# Controller.net
KiCad netlist of a schematic drawn in Altium Designer
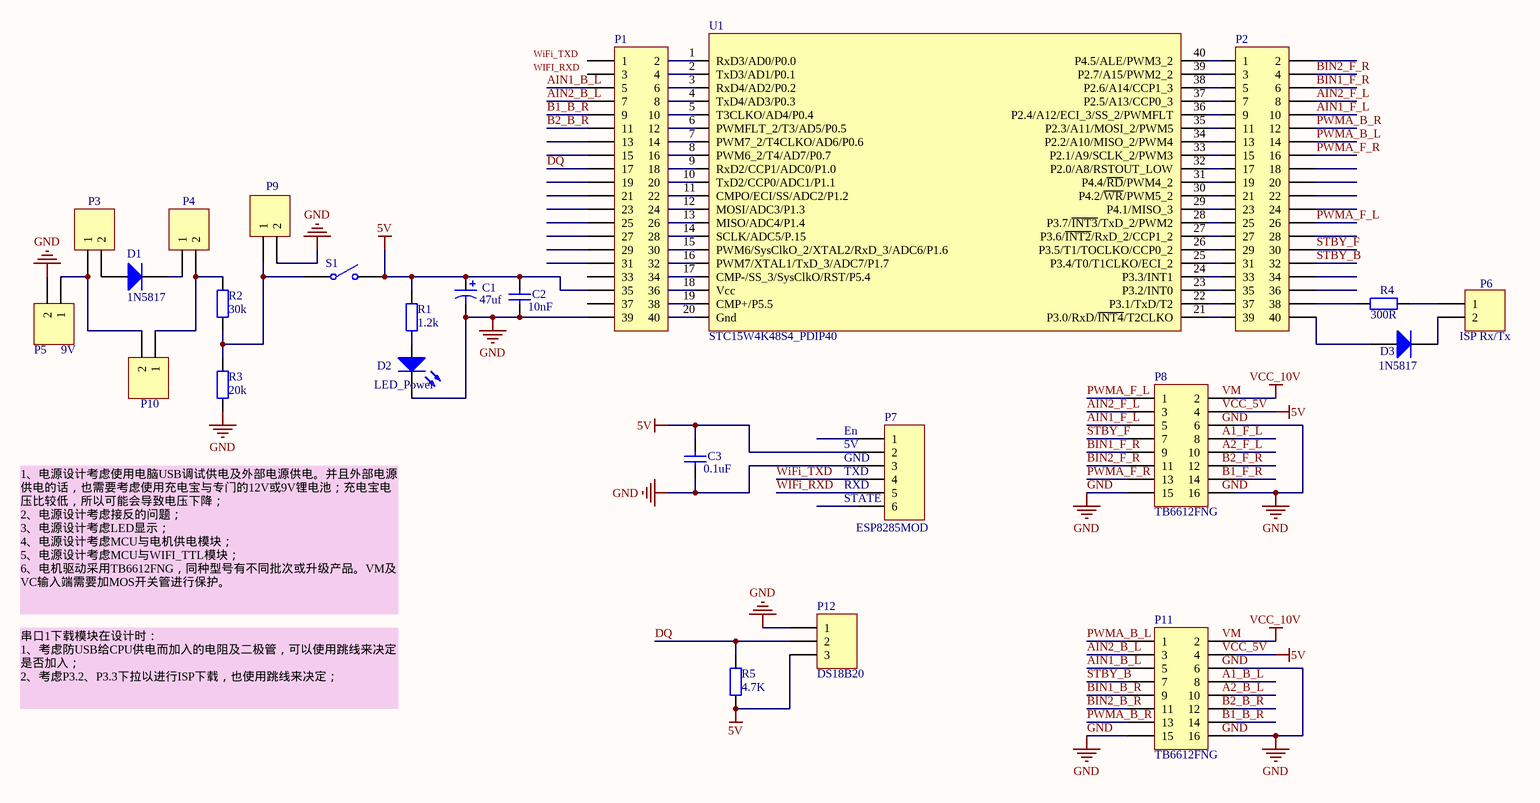
[diagram p0: Controller.SchDoc]

(export (version "E")
  (design (tool "Eeschema 10.0.6"))
  (components
    (comp (ref "C1")
      (value "47uf")
      (footprint "RB7.6-15")
      (description "Polarized Capacitor (Radial)")
      (fields (field (name "Comment") "Cap Pol1") (field (name "PUBLISHER") "Altium Limited"))
      (libsource (lib "Miscellaneous Devices") (part "Cap Pol1"))
    )
    (comp (ref "C2")
      (value "10nF")
      (footprint "RAD-0.3")
      (description "Capacitor")
      (fields (field (name "Comment") "Cap") (field (name "PUBLISHER") "Altium Limited"))
      (libsource (lib "Miscellaneous Devices") (part "Cap"))
    )
    (comp (ref "C3")
      (value "0.1uF")
      (footprint "RAD-0.3")
      (description "Capacitor")
      (fields (field (name "Comment") "Cap") (field (name "PUBLISHER") "Altium Limited"))
      (libsource (lib "Miscellaneous Devices") (part "Cap"))
    )
    (comp (ref "D1")
      (value "1N5817")
      (footprint "DO-35")
      (description "High Conductance Fast Diode")
      (fields (field (name "PUBLISHER") "Altium Limited"))
      (libsource (lib "Miscellaneous Devices") (part "Diode 1N914"))
    )
    (comp (ref "D2")
      (value "LED_Power")
      (footprint "LED-0")
      (description "Typical INFRARED GaAs LED")
      (fields (field (name "PUBLISHER") "Altium Limited"))
      (libsource (lib "Miscellaneous Devices") (part "LED0"))
    )
    (comp (ref "D3")
      (value "1N5817")
      (footprint "DO-35")
      (description "High Conductance Fast Diode")
      (fields (field (name "PUBLISHER") "Altium Limited"))
      (libsource (lib "Miscellaneous Devices") (part "Diode 1N914"))
    )
    (comp (ref "P1")
      (value "Header 20X2")
      (footprint "HDR2X20")
      (description "Header, 20-Pin, Dual row")
      (fields (field (name "PUBLISHER") "Altium Limited"))
      (libsource (lib "Miscellaneous Connectors") (part "Header 20X2"))
    )
    (comp (ref "P2")
      (value "Header 20X2")
      (footprint "HDR2X20")
      (description "Header, 20-Pin, Dual row")
      (fields (field (name "PUBLISHER") "Altium Limited"))
      (libsource (lib "Miscellaneous Connectors") (part "Header 20X2"))
    )
    (comp (ref "P3")
      (value "Header 2")
      (footprint "HDR1X2")
      (description "Header, 2-Pin")
      (fields (field (name "PUBLISHER") "Altium Limited"))
      (libsource (lib "Miscellaneous Connectors") (part "Header 2"))
    )
    (comp (ref "P4")
      (value "Header 2")
      (footprint "HDR1X2")
      (description "Header, 2-Pin")
      (fields (field (name "PUBLISHER") "Altium Limited"))
      (libsource (lib "Miscellaneous Connectors") (part "Header 2"))
    )
    (comp (ref "P5")
      (value "9V")
      (footprint "HDR1X2")
      (description "Header, 2-Pin")
      (fields (field (name "PUBLISHER") "Altium Limited"))
      (libsource (lib "") (part "Header 2_1"))
    )
    (comp (ref "P6")
      (value "ISP Rx/Tx")
      (footprint "HDR1X2")
      (description "Header, 2-Pin")
      (fields (field (name "PUBLISHER") "Altium Limited"))
      (libsource (lib "") (part "Header 2_2"))
    )
    (comp (ref "P7")
      (value "ESP8285MOD")
      (footprint "HDR1X6")
      (description "Header, 6-Pin")
      (fields (field (name "PUBLISHER") "Altium Limited"))
      (libsource (lib "Miscellaneous Connectors") (part "Header 6"))
    )
    (comp (ref "P8")
      (value "TB6612FNG")
      (footprint "HDR2X8")
      (description "Header, 8-Pin, Dual row")
      (fields (field (name "PUBLISHER") "Altium Limited"))
      (libsource (lib "Miscellaneous Connectors") (part "Header 8X2"))
    )
    (comp (ref "P9")
      (value "Header 2")
      (footprint "HDR1X2")
      (description "Header, 2-Pin")
      (fields (field (name "PUBLISHER") "Altium Limited"))
      (libsource (lib "Miscellaneous Connectors") (part "Header 2"))
    )
    (comp (ref "P10")
      (value "Header 2")
      (footprint "HDR1X2")
      (description "Header, 2-Pin")
      (fields (field (name "PUBLISHER") "Altium Limited"))
      (libsource (lib "") (part "Header 2_1"))
    )
    (comp (ref "P11")
      (value "TB6612FNG")
      (footprint "HDR2X8")
      (description "Header, 8-Pin, Dual row")
      (fields (field (name "PUBLISHER") "Altium Limited"))
      (libsource (lib "Miscellaneous Connectors") (part "Header 8X2"))
    )
    (comp (ref "P12")
      (value "DS18B20")
      (footprint "HDR1X3")
      (description "Header, 3-Pin")
      (fields (field (name "PUBLISHER") "Altium Limited"))
      (libsource (lib "Miscellaneous Connectors") (part "Header 3"))
    )
    (comp (ref "R1")
      (value "1.2k")
      (footprint "AXIAL-0.4")
      (description "Resistor")
      (fields (field (name "Comment") "Res2") (field (name "PUBLISHER") "Altium Limited"))
      (libsource (lib "") (part "Res2_1"))
    )
    (comp (ref "R2")
      (value "30k")
      (footprint "AXIAL-0.4")
      (description "Resistor")
      (fields (field (name "Comment") "Res2") (field (name "PUBLISHER") "Altium Limited"))
      (libsource (lib "Miscellaneous Devices") (part "Res2"))
    )
    (comp (ref "R3")
      (value "20k")
      (footprint "AXIAL-0.4")
      (description "Resistor")
      (fields (field (name "Comment") "Res2") (field (name "PUBLISHER") "Altium Limited"))
      (libsource (lib "Miscellaneous Devices") (part "Res2"))
    )
    (comp (ref "R4")
      (value "300R")
      (footprint "AXIAL-0.4")
      (description "Resistor")
      (fields (field (name "Comment") "Res2") (field (name "PUBLISHER") "Altium Limited"))
      (libsource (lib "") (part "Res2_2"))
    )
    (comp (ref "R5")
      (value "4.7K")
      (footprint "AXIAL-0.4")
      (description "Resistor")
      (fields (field (name "Comment") "Res2") (field (name "PUBLISHER") "Altium Limited"))
      (libsource (lib "") (part "Res2_1"))
    )
    (comp (ref "S1")
      (value "SW-SPST")
      (footprint "SPST-2")
      (description "Single-Pole, Single-Throw Switch")
      (fields (field (name "PUBLISHER") "Altium Limited"))
      (libsource (lib "Miscellaneous Devices") (part "SW-SPST"))
    )
    (comp (ref "U1")
      (value "STC15W4K48S4_PDIP40")
      (footprint "STC15W4K48S4_DIP40")
      (description "STC15W4K48S4")
      (libsource (lib "yangliwei_integrated_Library") (part "STC15W4K48S4_PDIP40"))
    )
  )
  (nets
    (net (code "5") (name "/AIN1_B_L") (class "Default")
      (node (ref "P1") (pin "5") (pinfunction "5_5") (pintype "passive"))
      (node (ref "P11") (pin "5") (pinfunction "5_5") (pintype "passive"))
    )
    (net (code "6") (name "/AIN1_F_L") (class "Default")
      (node (ref "P2") (pin "10") (pinfunction "10_10") (pintype "passive"))
      (node (ref "P8") (pin "5") (pinfunction "5_5") (pintype "passive"))
    )
    (net (code "7") (name "/AIN2_B_L") (class "Default")
      (node (ref "P1") (pin "7") (pinfunction "7_7") (pintype "passive"))
      (node (ref "P11") (pin "3") (pinfunction "3_3") (pintype "passive"))
    )
    (net (code "8") (name "/AIN2_F_L") (class "Default")
      (node (ref "P2") (pin "8") (pinfunction "8_8") (pintype "passive"))
      (node (ref "P8") (pin "3") (pinfunction "3_3") (pintype "passive"))
    )
    (net (code "9") (name "/B1_B_R") (class "Default")
      (node (ref "P1") (pin "9") (pinfunction "9_9") (pintype "passive"))
    )
    (net (code "11") (name "/B2_B_R") (class "Default")
      (node (ref "P1") (pin "11") (pinfunction "11_11") (pintype "passive"))
    )
    (net (code "13") (name "/BIN1_B_R") (class "Default")
      (node (ref "P11") (pin "9") (pinfunction "9_9") (pintype "passive"))
    )
    (net (code "14") (name "/BIN1_F_R") (class "Default")
      (node (ref "P2") (pin "6") (pinfunction "6_6") (pintype "passive"))
      (node (ref "P8") (pin "9") (pinfunction "9_9") (pintype "passive"))
    )
    (net (code "15") (name "/BIN2_B_R") (class "Default")
      (node (ref "P11") (pin "11") (pinfunction "11_11") (pintype "passive"))
    )
    (net (code "16") (name "/BIN2_F_R") (class "Default")
      (node (ref "P2") (pin "4") (pinfunction "4_4") (pintype "passive"))
      (node (ref "P8") (pin "11") (pinfunction "11_11") (pintype "passive"))
    )
    (net (code "17") (name "/DQ") (class "Default")
      (node (ref "P1") (pin "17") (pinfunction "17_17") (pintype "passive"))
      (node (ref "P12") (pin "2") (pinfunction "2_2") (pintype "passive"))
      (node (ref "R5") (pin "1") (pinfunction "1_1") (pintype "passive"))
    )
    (net (code "18") (name "/PWMA_B_L") (class "Default")
      (node (ref "P11") (pin "1") (pinfunction "1_1") (pintype "passive"))
      (node (ref "P2") (pin "14") (pinfunction "14_14") (pintype "passive"))
    )
    (net (code "19") (name "/PWMA_B_R") (class "Default")
      (node (ref "P11") (pin "13") (pinfunction "13_13") (pintype "passive"))
      (node (ref "P2") (pin "12") (pinfunction "12_12") (pintype "passive"))
    )
    (net (code "20") (name "/PWMA_F_L") (class "Default")
      (node (ref "P2") (pin "26") (pinfunction "26_26") (pintype "passive"))
      (node (ref "P8") (pin "1") (pinfunction "1_1") (pintype "passive"))
    )
    (net (code "21") (name "/PWMA_F_R") (class "Default")
      (node (ref "P2") (pin "16") (pinfunction "16_16") (pintype "passive"))
      (node (ref "P8") (pin "13") (pinfunction "13_13") (pintype "passive"))
    )
    (net (code "22") (name "/STBY_B") (class "Default")
      (node (ref "P11") (pin "7") (pinfunction "7_7") (pintype "passive"))
      (node (ref "P2") (pin "32") (pinfunction "32_32") (pintype "passive"))
    )
    (net (code "23") (name "/STBY_F") (class "Default")
      (node (ref "P2") (pin "30") (pinfunction "30_30") (pintype "passive"))
      (node (ref "P8") (pin "7") (pinfunction "7_7") (pintype "passive"))
    )
    (net (code "27") (name "/WIFi_RXD") (class "Default")
      (node (ref "P7") (pin "5") (pinfunction "5_5") (pintype "passive"))
    )
    (net (code "28") (name "/WiFi_TXD") (class "Default")
      (node (ref "P7") (pin "4") (pinfunction "4_4") (pintype "passive"))
    )
    (net (code "29") (name "5V") (class "Default")
      (node (ref "C1") (pin "1") (pinfunction "1_1") (pintype "passive"))
      (node (ref "C2") (pin "2") (pinfunction "2_2") (pintype "passive"))
      (node (ref "C3") (pin "2") (pinfunction "2_2") (pintype "passive"))
      (node (ref "P1") (pin "35") (pinfunction "35_35") (pintype "passive"))
      (node (ref "P11") (pin "4") (pinfunction "4_4") (pintype "passive"))
      (node (ref "P12") (pin "3") (pinfunction "3_3") (pintype "passive"))
      (node (ref "P7") (pin "2") (pinfunction "2_2") (pintype "passive"))
      (node (ref "P8") (pin "4") (pinfunction "4_4") (pintype "passive"))
      (node (ref "R1") (pin "1") (pinfunction "1_1") (pintype "passive"))
      (node (ref "R5") (pin "2") (pinfunction "2_2") (pintype "passive"))
      (node (ref "S1") (pin "2") (pinfunction "NO_2") (pintype "passive"))
    )
    (net (code "30") (name "GND") (class "Default")
      (node (ref "C1") (pin "2") (pinfunction "2_2") (pintype "passive"))
      (node (ref "C2") (pin "1") (pinfunction "1_1") (pintype "passive"))
      (node (ref "C3") (pin "1") (pinfunction "1_1") (pintype "passive"))
      (node (ref "D2") (pin "2") (pinfunction "K_2") (pintype "passive"))
      (node (ref "P1") (pin "39") (pinfunction "39_39") (pintype "passive"))
      (node (ref "P11") (pin "15") (pinfunction "15_15") (pintype "passive"))
      (node (ref "P11") (pin "16") (pinfunction "16_16") (pintype "passive"))
      (node (ref "P11") (pin "6") (pinfunction "6_6") (pintype "passive"))
      (node (ref "P12") (pin "1") (pinfunction "1_1") (pintype "passive"))
      (node (ref "P5") (pin "2") (pinfunction "2_2") (pintype "passive"))
      (node (ref "P7") (pin "3") (pinfunction "3_3") (pintype "passive"))
      (node (ref "P8") (pin "15") (pinfunction "15_15") (pintype "passive"))
      (node (ref "P8") (pin "16") (pinfunction "16_16") (pintype "passive"))
      (node (ref "P8") (pin "6") (pinfunction "6_6") (pintype "passive"))
      (node (ref "P9") (pin "2") (pinfunction "2_2") (pintype "passive"))
      (node (ref "R3") (pin "1") (pinfunction "1_1") (pintype "passive"))
    )
    (net (code "31") (name "Net-(D1-A)") (class "Default")
      (node (ref "D1") (pin "1") (pinfunction "A_1") (pintype "passive"))
      (node (ref "P3") (pin "2") (pinfunction "2_2") (pintype "passive"))
    )
    (net (code "32") (name "Net-(D1-K)") (class "Default")
      (node (ref "D1") (pin "2") (pinfunction "K_2") (pintype "passive"))
      (node (ref "P4") (pin "1") (pinfunction "1_1") (pintype "passive"))
    )
    (net (code "33") (name "Net-(D2-A)") (class "Default")
      (node (ref "D2") (pin "1") (pinfunction "A_1") (pintype "passive"))
      (node (ref "R1") (pin "2") (pinfunction "2_2") (pintype "passive"))
    )
    (net (code "34") (name "Net-(D3-A)") (class "Default")
      (node (ref "D3") (pin "1") (pinfunction "A_1") (pintype "passive"))
      (node (ref "P2") (pin "40") (pinfunction "40_40") (pintype "passive"))
    )
    (net (code "35") (name "Net-(D3-K)") (class "Default")
      (node (ref "D3") (pin "2") (pinfunction "K_2") (pintype "passive"))
      (node (ref "P6") (pin "2") (pinfunction "2_2") (pintype "passive"))
    )
    (net (code "36") (name "Net-(P2-Pad38)") (class "Default")
      (node (ref "P2") (pin "38") (pinfunction "38_38") (pintype "passive"))
      (node (ref "R4") (pin "1") (pinfunction "1_1") (pintype "passive"))
    )
    (net (code "37") (name "Net-(P6-Pad1)") (class "Default")
      (node (ref "P6") (pin "1") (pinfunction "1_1") (pintype "passive"))
      (node (ref "R4") (pin "2") (pinfunction "2_2") (pintype "passive"))
    )
    (net (code "38") (name "Net-(P10-Pad1)") (class "Default")
      (node (ref "P10") (pin "1") (pinfunction "1_1") (pintype "passive"))
      (node (ref "P4") (pin "2") (pinfunction "2_2") (pintype "passive"))
      (node (ref "R2") (pin "2") (pinfunction "2_2") (pintype "passive"))
    )
    (net (code "39") (name "Net-(P10-Pad2)") (class "Default")
      (node (ref "P10") (pin "2") (pinfunction "2_2") (pintype "passive"))
      (node (ref "P3") (pin "1") (pinfunction "1_1") (pintype "passive"))
      (node (ref "P5") (pin "1") (pinfunction "1_1") (pintype "passive"))
    )
    (net (code "40") (name "Net-(S1-COMMON)") (class "Default")
      (node (ref "P9") (pin "1") (pinfunction "1_1") (pintype "passive"))
      (node (ref "R2") (pin "1") (pinfunction "1_1") (pintype "passive"))
      (node (ref "R3") (pin "2") (pinfunction "2_2") (pintype "passive"))
      (node (ref "S1") (pin "1") (pinfunction "COMMON_1") (pintype "passive"))
    )
    (net (code "41") (name "Net-(U1-CMP+{slash}P5.5)") (class "Default")
      (node (ref "P1") (pin "38") (pinfunction "38_38") (pintype "passive"))
      (node (ref "U1") (pin "19") (pinfunction "CMP+/P5.5_19") (pintype "passive"))
    )
    (net (code "42") (name "Net-(U1-CMP-{slash}SS_3{slash}SysClkO{slash}RST{slash}P5.4)") (class "Default")
      (node (ref "P1") (pin "34") (pinfunction "34_34") (pintype "passive"))
      (node (ref "U1") (pin "17") (pinfunction "CMP-/SS_3/SysClkO/RST/P5.4_17") (pintype "passive"))
    )
    (net (code "43") (name "Net-(U1-CMPO{slash}ECI{slash}SS{slash}ADC2{slash}P1.2)") (class "Default")
      (node (ref "P1") (pin "22") (pinfunction "22_22") (pintype "passive"))
      (node (ref "U1") (pin "11") (pinfunction "CMPO/ECI/SS/ADC2/P1.2_11") (pintype "passive"))
    )
    (net (code "44") (name "Net-(U1-Gnd)") (class "Default")
      (node (ref "P1") (pin "40") (pinfunction "40_40") (pintype "passive"))
      (node (ref "U1") (pin "20") (pinfunction "Gnd_20") (pintype "passive"))
    )
    (net (code "45") (name "Net-(U1-MISO{slash}ADC4{slash}P1.4)") (class "Default")
      (node (ref "P1") (pin "26") (pinfunction "26_26") (pintype "passive"))
      (node (ref "U1") (pin "13") (pinfunction "MISO/ADC4/P1.4_13") (pintype "passive"))
    )
    (net (code "46") (name "Net-(U1-MOSI{slash}ADC3{slash}P1.3)") (class "Default")
      (node (ref "P1") (pin "24") (pinfunction "24_24") (pintype "passive"))
      (node (ref "U1") (pin "12") (pinfunction "MOSI/ADC3/P1.3_12") (pintype "passive"))
    )
    (net (code "47") (name "Net-(U1-P2.0{slash}A8{slash}RSTOUT_LOW)") (class "Default")
      (node (ref "P2") (pin "17") (pinfunction "17_17") (pintype "passive"))
      (node (ref "U1") (pin "32") (pinfunction "P2.0/A8/RSTOUT_LOW_32") (pintype "passive"))
    )
    (net (code "48") (name "Net-(U1-P2.1{slash}A9{slash}SCLK_2{slash}PWM3)") (class "Default")
      (node (ref "P2") (pin "15") (pinfunction "15_15") (pintype "passive"))
      (node (ref "U1") (pin "33") (pinfunction "P2.1/A9/SCLK_2/PWM3_33") (pintype "passive"))
    )
    (net (code "49") (name "Net-(U1-P2.2{slash}A10{slash}MISO_2{slash}PWM4)") (class "Default")
      (node (ref "P2") (pin "13") (pinfunction "13_13") (pintype "passive"))
      (node (ref "U1") (pin "34") (pinfunction "P2.2/A10/MISO_2/PWM4_34") (pintype "passive"))
    )
    (net (code "50") (name "Net-(U1-P2.3{slash}A11{slash}MOSI_2{slash}PWM5)") (class "Default")
      (node (ref "P2") (pin "11") (pinfunction "11_11") (pintype "passive"))
      (node (ref "U1") (pin "35") (pinfunction "P2.3/A11/MOSI_2/PWM5_35") (pintype "passive"))
    )
    (net (code "51") (name "Net-(U1-P2.4{slash}A12{slash}ECI_3{slash}SS_2{slash}PWMFLT)") (class "Default")
      (node (ref "P2") (pin "9") (pinfunction "9_9") (pintype "passive"))
      (node (ref "U1") (pin "36") (pinfunction "P2.4/A12/ECI_3/SS_2/PWMFLT_36") (pintype "passive"))
    )
    (net (code "52") (name "Net-(U1-P2.5{slash}A13{slash}CCP0_3)") (class "Default")
      (node (ref "P2") (pin "7") (pinfunction "7_7") (pintype "passive"))
      (node (ref "U1") (pin "37") (pinfunction "P2.5/A13/CCP0_3_37") (pintype "passive"))
    )
    (net (code "53") (name "Net-(U1-P2.6{slash}A14{slash}CCP1_3)") (class "Default")
      (node (ref "P2") (pin "5") (pinfunction "5_5") (pintype "passive"))
      (node (ref "U1") (pin "38") (pinfunction "P2.6/A14/CCP1_3_38") (pintype "passive"))
    )
    (net (code "54") (name "Net-(U1-P2.7{slash}A15{slash}PWM2_2)") (class "Default")
      (node (ref "P2") (pin "3") (pinfunction "3_3") (pintype "passive"))
      (node (ref "U1") (pin "39") (pinfunction "P2.7/A15/PWM2_2_39") (pintype "passive"))
    )
    (net (code "55") (name "Net-(U1-P3.0{slash}RxD{slash}~{INT4}{slash}T2CLKO)") (class "Default")
      (node (ref "P2") (pin "39") (pinfunction "39_39") (pintype "passive"))
      (node (ref "U1") (pin "21") (pinfunction "P3.0/RxD/~{INT4}/T2CLKO_21") (pintype "passive"))
    )
    (net (code "56") (name "Net-(U1-P3.1{slash}TxD{slash}T2)") (class "Default")
      (node (ref "P2") (pin "37") (pinfunction "37_37") (pintype "passive"))
      (node (ref "U1") (pin "22") (pinfunction "P3.1/TxD/T2_22") (pintype "passive"))
    )
    (net (code "57") (name "Net-(U1-P3.2{slash}INT0)") (class "Default")
      (node (ref "P2") (pin "35") (pinfunction "35_35") (pintype "passive"))
      (node (ref "U1") (pin "23") (pinfunction "P3.2/INT0_23") (pintype "passive"))
    )
    (net (code "58") (name "Net-(U1-P3.3{slash}INT1)") (class "Default")
      (node (ref "P2") (pin "33") (pinfunction "33_33") (pintype "passive"))
      (node (ref "U1") (pin "24") (pinfunction "P3.3/INT1_24") (pintype "passive"))
    )
    (net (code "59") (name "Net-(U1-P3.4{slash}T0{slash}T1CLKO{slash}ECI_2)") (class "Default")
      (node (ref "P2") (pin "31") (pinfunction "31_31") (pintype "passive"))
      (node (ref "U1") (pin "25") (pinfunction "P3.4/T0/T1CLKO/ECI_2_25") (pintype "passive"))
    )
    (net (code "60") (name "Net-(U1-P3.5{slash}T1{slash}TOCLKO{slash}CCP0_2)") (class "Default")
      (node (ref "P2") (pin "29") (pinfunction "29_29") (pintype "passive"))
      (node (ref "U1") (pin "26") (pinfunction "P3.5/T1/TOCLKO/CCP0_2_26") (pintype "passive"))
    )
    (net (code "61") (name "Net-(U1-P3.6{slash}~{INT2}{slash}RxD_2{slash}CCP1_2)") (class "Default")
      (node (ref "P2") (pin "27") (pinfunction "27_27") (pintype "passive"))
      (node (ref "U1") (pin "27") (pinfunction "P3.6/~{INT2}/RxD_2/CCP1_2_27") (pintype "passive"))
    )
    (net (code "62") (name "Net-(U1-P3.7{slash}~{INT3}{slash}TxD_2{slash}PWM2)") (class "Default")
      (node (ref "P2") (pin "25") (pinfunction "25_25") (pintype "passive"))
      (node (ref "U1") (pin "28") (pinfunction "P3.7/~{INT3}/TxD_2/PWM2_28") (pintype "passive"))
    )
    (net (code "63") (name "Net-(U1-P4.1{slash}MISO_3)") (class "Default")
      (node (ref "P2") (pin "23") (pinfunction "23_23") (pintype "passive"))
      (node (ref "U1") (pin "29") (pinfunction "P4.1/MISO_3_29") (pintype "passive"))
    )
    (net (code "64") (name "Net-(U1-P4.2{slash}~{WR}{slash}PWM5_2)") (class "Default")
      (node (ref "P2") (pin "21") (pinfunction "21_21") (pintype "passive"))
      (node (ref "U1") (pin "30") (pinfunction "P4.2/~{WR}/PWM5_2_30") (pintype "passive"))
    )
    (net (code "65") (name "Net-(U1-P4.4{slash}~{RD}{slash}PWM4_2)") (class "Default")
      (node (ref "P2") (pin "19") (pinfunction "19_19") (pintype "passive"))
      (node (ref "U1") (pin "31") (pinfunction "P4.4/~{RD}/PWM4_2_31") (pintype "passive"))
    )
    (net (code "66") (name "Net-(U1-P4.5{slash}ALE{slash}PWM3_2)") (class "Default")
      (node (ref "P2") (pin "1") (pinfunction "1_1") (pintype "passive"))
      (node (ref "U1") (pin "40") (pinfunction "P4.5/ALE/PWM3_2_40") (pintype "passive"))
    )
    (net (code "67") (name "Net-(U1-PWM6_2{slash}T4{slash}AD7{slash}P0.7)") (class "Default")
      (node (ref "P1") (pin "16") (pinfunction "16_16") (pintype "passive"))
      (node (ref "U1") (pin "8") (pinfunction "PWM6_2/T4/AD7/P0.7_8") (pintype "passive"))
    )
    (net (code "68") (name "Net-(U1-PWM6{slash}SysClkO_2{slash}XTAL2{slash}RxD_3{slash}ADC6{slash}P1.6)") (class "Default")
      (node (ref "P1") (pin "30") (pinfunction "30_30") (pintype "passive"))
      (node (ref "U1") (pin "15") (pinfunction "PWM6/SysClkO_2/XTAL2/RxD_3/ADC6/P1.6_15") (pintype "passive"))
    )
    (net (code "69") (name "Net-(U1-PWM7_2{slash}T4CLKO{slash}AD6{slash}P0.6)") (class "Default")
      (node (ref "P1") (pin "14") (pinfunction "14_14") (pintype "passive"))
      (node (ref "U1") (pin "7") (pinfunction "PWM7_2/T4CLKO/AD6/P0.6_7") (pintype "passive"))
    )
    (net (code "70") (name "Net-(U1-PWM7{slash}XTAL1{slash}TxD_3{slash}ADC7{slash}P1.7)") (class "Default")
      (node (ref "P1") (pin "32") (pinfunction "32_32") (pintype "passive"))
      (node (ref "U1") (pin "16") (pinfunction "PWM7/XTAL1/TxD_3/ADC7/P1.7_16") (pintype "passive"))
    )
    (net (code "71") (name "Net-(U1-PWMFLT_2{slash}T3{slash}AD5{slash}P0.5)") (class "Default")
      (node (ref "P1") (pin "12") (pinfunction "12_12") (pintype "passive"))
      (node (ref "U1") (pin "6") (pinfunction "PWMFLT_2/T3/AD5/P0.5_6") (pintype "passive"))
    )
    (net (code "72") (name "Net-(U1-RxD2{slash}CCP1{slash}ADC0{slash}P1.0)") (class "Default")
      (node (ref "P1") (pin "18") (pinfunction "18_18") (pintype "passive"))
      (node (ref "U1") (pin "9") (pinfunction "RxD2/CCP1/ADC0/P1.0_9") (pintype "passive"))
    )
    (net (code "73") (name "Net-(U1-RxD3{slash}AD0{slash}P0.0)") (class "Default")
      (node (ref "P1") (pin "2") (pinfunction "2_2") (pintype "passive"))
      (node (ref "U1") (pin "1") (pinfunction "RxD3/AD0/P0.0_1") (pintype "passive"))
    )
    (net (code "74") (name "Net-(U1-RxD4{slash}AD2{slash}P0.2)") (class "Default")
      (node (ref "P1") (pin "6") (pinfunction "6_6") (pintype "passive"))
      (node (ref "U1") (pin "3") (pinfunction "RxD4/AD2/P0.2_3") (pintype "passive"))
    )
    (net (code "75") (name "Net-(U1-SCLK{slash}ADC5{slash}P.15)") (class "Default")
      (node (ref "P1") (pin "28") (pinfunction "28_28") (pintype "passive"))
      (node (ref "U1") (pin "14") (pinfunction "SCLK/ADC5/P.15_14") (pintype "passive"))
    )
    (net (code "76") (name "Net-(U1-T3CLKO{slash}AD4{slash}P0.4)") (class "Default")
      (node (ref "P1") (pin "10") (pinfunction "10_10") (pintype "passive"))
      (node (ref "U1") (pin "5") (pinfunction "T3CLKO/AD4/P0.4_5") (pintype "passive"))
    )
    (net (code "77") (name "Net-(U1-TxD2{slash}CCP0{slash}ADC1{slash}P1.1)") (class "Default")
      (node (ref "P1") (pin "20") (pinfunction "20_20") (pintype "passive"))
      (node (ref "U1") (pin "10") (pinfunction "TxD2/CCP0/ADC1/P1.1_10") (pintype "passive"))
    )
    (net (code "78") (name "Net-(U1-TxD3{slash}AD1{slash}P0.1)") (class "Default")
      (node (ref "P1") (pin "4") (pinfunction "4_4") (pintype "passive"))
      (node (ref "U1") (pin "2") (pinfunction "TxD3/AD1/P0.1_2") (pintype "passive"))
    )
    (net (code "79") (name "Net-(U1-TxD4{slash}AD3{slash}P0.3)") (class "Default")
      (node (ref "P1") (pin "8") (pinfunction "8_8") (pintype "passive"))
      (node (ref "U1") (pin "4") (pinfunction "TxD4/AD3/P0.3_4") (pintype "passive"))
    )
    (net (code "80") (name "Net-(U1-Vcc)") (class "Default")
      (node (ref "P1") (pin "36") (pinfunction "36_36") (pintype "passive"))
      (node (ref "U1") (pin "18") (pinfunction "Vcc_18") (pintype "passive"))
    )
    (net (code "81") (name "VCC_10V") (class "Default")
      (node (ref "P11") (pin "2") (pinfunction "2_2") (pintype "passive"))
      (node (ref "P8") (pin "2") (pinfunction "2_2") (pintype "passive"))
    )
    (net (code "82") (name "unconnected-(P1-Pad1)") (class "Default")
      (node (ref "P1") (pin "1") (pinfunction "1_1") (pintype "passive"))
    )
    (net (code "83") (name "unconnected-(P1-Pad3)") (class "Default")
      (node (ref "P1") (pin "3") (pinfunction "3_3") (pintype "passive"))
    )
    (net (code "84") (name "unconnected-(P1-Pad13)") (class "Default")
      (node (ref "P1") (pin "13") (pinfunction "13_13") (pintype "passive"))
    )
    (net (code "85") (name "unconnected-(P1-Pad15)") (class "Default")
      (node (ref "P1") (pin "15") (pinfunction "15_15") (pintype "passive"))
    )
    (net (code "86") (name "unconnected-(P1-Pad19)") (class "Default")
      (node (ref "P1") (pin "19") (pinfunction "19_19") (pintype "passive"))
    )
    (net (code "87") (name "unconnected-(P1-Pad21)") (class "Default")
      (node (ref "P1") (pin "21") (pinfunction "21_21") (pintype "passive"))
    )
    (net (code "88") (name "unconnected-(P1-Pad23)") (class "Default")
      (node (ref "P1") (pin "23") (pinfunction "23_23") (pintype "passive"))
    )
    (net (code "89") (name "unconnected-(P1-Pad25)") (class "Default")
      (node (ref "P1") (pin "25") (pinfunction "25_25") (pintype "passive"))
    )
    (net (code "90") (name "unconnected-(P1-Pad27)") (class "Default")
      (node (ref "P1") (pin "27") (pinfunction "27_27") (pintype "passive"))
    )
    (net (code "91") (name "unconnected-(P1-Pad29)") (class "Default")
      (node (ref "P1") (pin "29") (pinfunction "29_29") (pintype "passive"))
    )
    (net (code "92") (name "unconnected-(P1-Pad31)") (class "Default")
      (node (ref "P1") (pin "31") (pinfunction "31_31") (pintype "passive"))
    )
    (net (code "93") (name "unconnected-(P1-Pad33)") (class "Default")
      (node (ref "P1") (pin "33") (pinfunction "33_33") (pintype "passive"))
    )
    (net (code "94") (name "unconnected-(P1-Pad37)") (class "Default")
      (node (ref "P1") (pin "37") (pinfunction "37_37") (pintype "passive"))
    )
    (net (code "95") (name "unconnected-(P2-Pad2)") (class "Default")
      (node (ref "P2") (pin "2") (pinfunction "2_2") (pintype "passive"))
    )
    (net (code "96") (name "unconnected-(P2-Pad18)") (class "Default")
      (node (ref "P2") (pin "18") (pinfunction "18_18") (pintype "passive"))
    )
    (net (code "97") (name "unconnected-(P2-Pad20)") (class "Default")
      (node (ref "P2") (pin "20") (pinfunction "20_20") (pintype "passive"))
    )
    (net (code "98") (name "unconnected-(P2-Pad22)") (class "Default")
      (node (ref "P2") (pin "22") (pinfunction "22_22") (pintype "passive"))
    )
    (net (code "99") (name "unconnected-(P2-Pad24)") (class "Default")
      (node (ref "P2") (pin "24") (pinfunction "24_24") (pintype "passive"))
    )
    (net (code "100") (name "unconnected-(P2-Pad28)") (class "Default")
      (node (ref "P2") (pin "28") (pinfunction "28_28") (pintype "passive"))
    )
    (net (code "101") (name "unconnected-(P2-Pad34)") (class "Default")
      (node (ref "P2") (pin "34") (pinfunction "34_34") (pintype "passive"))
    )
    (net (code "102") (name "unconnected-(P2-Pad36)") (class "Default")
      (node (ref "P2") (pin "36") (pinfunction "36_36") (pintype "passive"))
    )
    (net (code "103") (name "unconnected-(P7-Pad1)") (class "Default")
      (node (ref "P7") (pin "1") (pinfunction "1_1") (pintype "passive"))
    )
    (net (code "104") (name "unconnected-(P7-Pad6)") (class "Default")
      (node (ref "P7") (pin "6") (pinfunction "6_6") (pintype "passive"))
    )
    (net (code "105") (name "unconnected-(P8-Pad8)") (class "Default")
      (node (ref "P8") (pin "8") (pinfunction "8_8") (pintype "passive"))
    )
    (net (code "106") (name "unconnected-(P8-Pad10)") (class "Default")
      (node (ref "P8") (pin "10") (pinfunction "10_10") (pintype "passive"))
    )
    (net (code "107") (name "unconnected-(P8-Pad12)") (class "Default")
      (node (ref "P8") (pin "12") (pinfunction "12_12") (pintype "passive"))
    )
    (net (code "108") (name "unconnected-(P8-Pad14)") (class "Default")
      (node (ref "P8") (pin "14") (pinfunction "14_14") (pintype "passive"))
    )
    (net (code "109") (name "unconnected-(P11-Pad8)") (class "Default")
      (node (ref "P11") (pin "8") (pinfunction "8_8") (pintype "passive"))
    )
    (net (code "110") (name "unconnected-(P11-Pad10)") (class "Default")
      (node (ref "P11") (pin "10") (pinfunction "10_10") (pintype "passive"))
    )
    (net (code "111") (name "unconnected-(P11-Pad12)") (class "Default")
      (node (ref "P11") (pin "12") (pinfunction "12_12") (pintype "passive"))
    )
    (net (code "112") (name "unconnected-(P11-Pad14)") (class "Default")
      (node (ref "P11") (pin "14") (pinfunction "14_14") (pintype "passive"))
    )
  )
)
